# power_converter.net
KiCad netlist of a schematic drawn in EAGLE
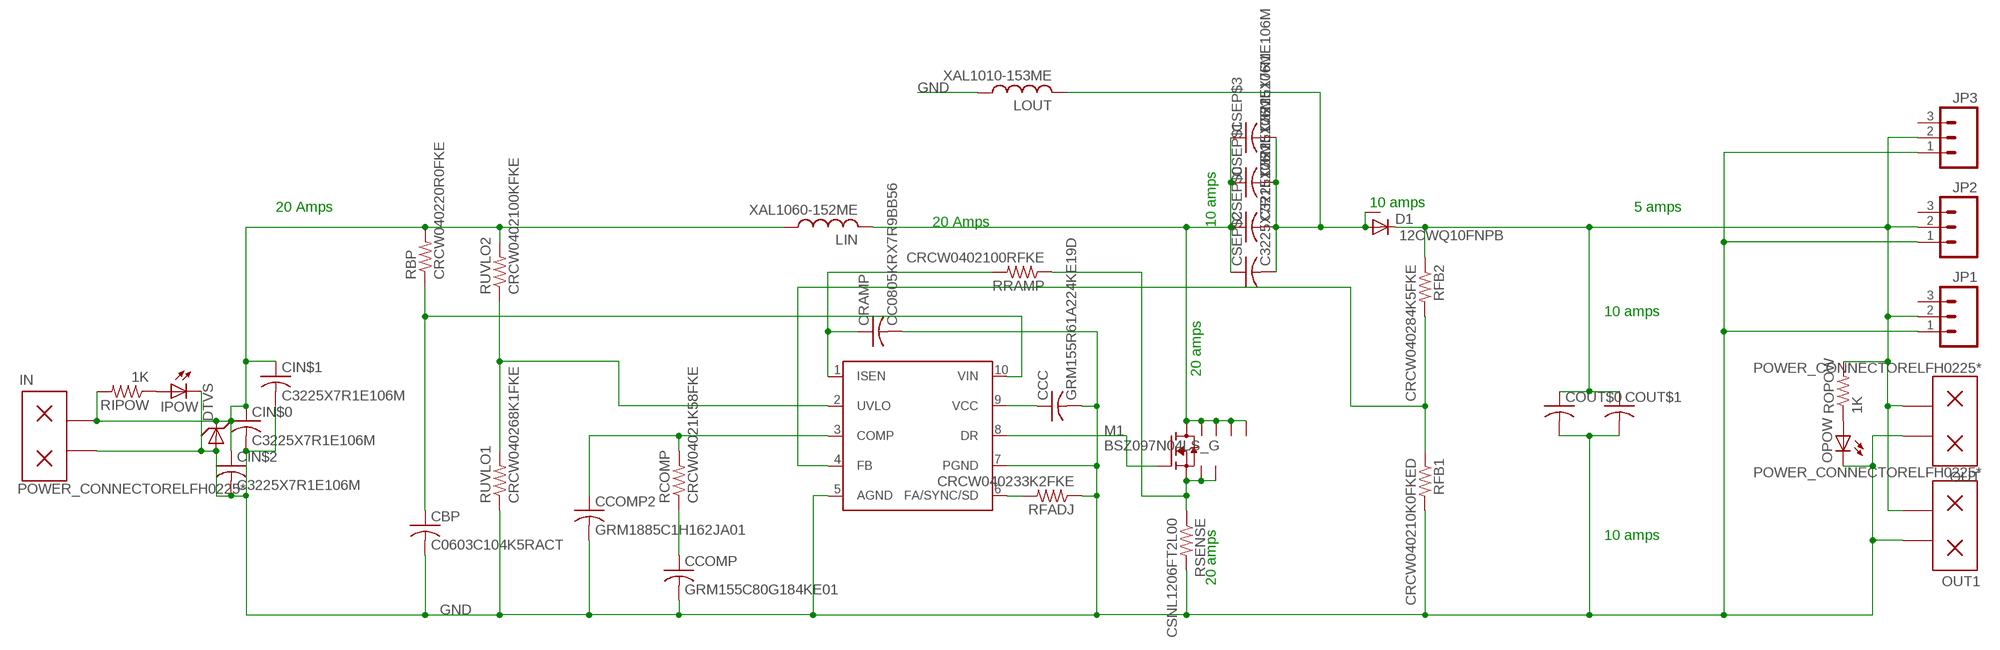
[diagram p0: schematic, sheet 1]

(export (version "E")
  (design (tool "Eeschema 10.0.6"))
  (components
    (comp (ref "CBP")
      (value "C0603C104K5RACT")
      (footprint "eagle-import:C0603")
      (libsource (lib "eagle-import") (part "resistor_C-USC0603"))
    )
    (comp (ref "CCC")
      (value "GRM155R61A224KE19D")
      (footprint "eagle-import:C0402")
      (libsource (lib "eagle-import") (part "resistor_C-USC0402"))
    )
    (comp (ref "CCOMP")
      (value "GRM155C80G184KE01")
      (footprint "eagle-import:C0402")
      (libsource (lib "eagle-import") (part "resistor_C-USC0402"))
    )
    (comp (ref "CCOMP2")
      (value "GRM1885C1H162JA01")
      (footprint "eagle-import:C0603")
      (libsource (lib "eagle-import") (part "resistor_C-USC0603"))
    )
    (comp (ref "CIN$0")
      (value "C3225X7R1E106M")
      (footprint "eagle-import:C1210")
      (libsource (lib "eagle-import") (part "resistor_C-USC1210"))
    )
    (comp (ref "CIN$1")
      (value "C3225X7R1E106M")
      (footprint "eagle-import:C1210")
      (libsource (lib "eagle-import") (part "resistor_C-USC1210"))
    )
    (comp (ref "CIN$2")
      (value "C3225X7R1E106M")
      (footprint "eagle-import:C1210")
      (libsource (lib "eagle-import") (part "resistor_C-USC1210"))
    )
    (comp (ref "COUT$0")
      (value "C-USRR71C331MDN1")
      (footprint "eagle-import:RR71C331MDN1")
      (libsource (lib "eagle-import") (part "C-USRR71C331MDN1"))
    )
    (comp (ref "COUT$1")
      (value "C-USRR71C331MDN1")
      (footprint "eagle-import:RR71C331MDN1")
      (libsource (lib "eagle-import") (part "C-USRR71C331MDN1"))
    )
    (comp (ref "CRAMP")
      (value "CC0805KRX7R9BB56")
      (footprint "eagle-import:C0805")
      (libsource (lib "eagle-import") (part "resistor_C-USC0805"))
    )
    (comp (ref "CSEP$0")
      (value "C3225X7R1E106M")
      (footprint "eagle-import:C1210")
      (libsource (lib "eagle-import") (part "resistor_C-USC1210"))
    )
    (comp (ref "CSEP$1")
      (value "C3225X7R1E106M")
      (footprint "eagle-import:C1210")
      (libsource (lib "eagle-import") (part "resistor_C-USC1210"))
    )
    (comp (ref "CSEP$2")
      (value "C3225X7R1E106M")
      (footprint "eagle-import:C1210")
      (libsource (lib "eagle-import") (part "resistor_C-USC1210"))
    )
    (comp (ref "CSEP$3")
      (value "C3225X7R1E106M")
      (footprint "eagle-import:C1210")
      (libsource (lib "eagle-import") (part "resistor_C-USC1210"))
    )
    (comp (ref "D1")
      (value "12CWQ10FNPB")
      (footprint "eagle-import:D-PAK")
      (libsource (lib "eagle-import") (part "VS-12CWQ10FNPBF"))
    )
    (comp (ref "DTVS")
      (value "MMSZ5246BT1G")
      (footprint "eagle-import:SOD-123")
      (libsource (lib "eagle-import") (part "MMSZ5242BT1G"))
    )
    (comp (ref "IN")
      (value "POWER_CONNECTORELFH0225*")
      (footprint "eagle-import:ELFH0225_")
      (libsource (lib "eagle-import") (part "POWER_CONNECTORELFH0225"))
    )
    (comp (ref "IPOW")
      (value "LEDCHIPLED_0805")
      (footprint "eagle-import:CHIPLED_0805")
      (libsource (lib "eagle-import") (part "LEDCHIPLED_0805"))
    )
    (comp (ref "JP1")
      (value "M03PTH")
      (footprint "eagle-import:1X03")
      (libsource (lib "eagle-import") (part "M03PTH"))
    )
    (comp (ref "JP2")
      (value "M03PTH")
      (footprint "eagle-import:1X03")
      (libsource (lib "eagle-import") (part "M03PTH"))
    )
    (comp (ref "JP3")
      (value "M03PTH")
      (footprint "eagle-import:1X03")
      (libsource (lib "eagle-import") (part "M03PTH"))
    )
    (comp (ref "LIN")
      (value "XAL1060-152ME")
      (footprint "eagle-import:1060-152")
      (libsource (lib "eagle-import") (part "L-US1060-152"))
    )
    (comp (ref "LOUT")
      (value "XAL1010-153ME")
      (footprint "eagle-import:1010-153")
      (libsource (lib "eagle-import") (part "L-US1010-153"))
    )
    (comp (ref "M1")
      (value "BSZ097N04LS_G")
      (footprint "eagle-import:PG-TSDSON8")
      (libsource (lib "eagle-import") (part "BSZ097N04LS_G"))
    )
    (comp (ref "OPOW")
      (value "LEDCHIPLED_0805")
      (footprint "eagle-import:CHIPLED_0805")
      (libsource (lib "eagle-import") (part "LEDCHIPLED_0805"))
    )
    (comp (ref "OUT")
      (value "POWER_CONNECTORELFH0225*")
      (footprint "eagle-import:ELFH0225_")
      (libsource (lib "eagle-import") (part "POWER_CONNECTORELFH0225"))
    )
    (comp (ref "OUT1")
      (value "POWER_CONNECTORELFH0225*")
      (footprint "eagle-import:ELFH0225_")
      (libsource (lib "eagle-import") (part "POWER_CONNECTORELFH0225"))
    )
    (comp (ref "RBP")
      (value "CRCW040220R0FKE")
      (footprint "eagle-import:R0402")
      (libsource (lib "eagle-import") (part "R-US_R0402"))
    )
    (comp (ref "RCOMP")
      (value "CRCW04021K58FKE")
      (footprint "eagle-import:R0402")
      (libsource (lib "eagle-import") (part "R-US_R0402"))
    )
    (comp (ref "RFADJ")
      (value "CRCW040233K2FKE")
      (footprint "eagle-import:R0402")
      (libsource (lib "eagle-import") (part "R-US_R0402"))
    )
    (comp (ref "RFB1")
      (value "CRCW040210K0FKED")
      (footprint "eagle-import:R0402")
      (libsource (lib "eagle-import") (part "R-US_R0402"))
    )
    (comp (ref "RFB2")
      (value "CRCW040284K5FKE")
      (footprint "eagle-import:R0402")
      (libsource (lib "eagle-import") (part "R-US_R0402"))
    )
    (comp (ref "RIPOW")
      (value "1K")
      (footprint "eagle-import:R1206")
      (libsource (lib "eagle-import") (part "R-US_R1206"))
    )
    (comp (ref "ROPOW")
      (value "1K")
      (footprint "eagle-import:R1206")
      (libsource (lib "eagle-import") (part "R-US_R1206"))
    )
    (comp (ref "RRAMP")
      (value "CRCW0402100RFKE")
      (footprint "eagle-import:R0402")
      (libsource (lib "eagle-import") (part "R-US_R0402"))
    )
    (comp (ref "RSENSE")
      (value "CSNL1206FT2L00")
      (footprint "eagle-import:M1206")
      (libsource (lib "eagle-import") (part "R-US_M1206"))
    )
    (comp (ref "RUVLO1")
      (value "CRCW040268K1FKE")
      (footprint "eagle-import:R0402")
      (libsource (lib "eagle-import") (part "R-US_R0402"))
    )
    (comp (ref "RUVLO2")
      (value "CRCW0402100KFKE")
      (footprint "eagle-import:R0402")
      (libsource (lib "eagle-import") (part "R-US_R0402"))
    )
    (comp (ref "U$1")
      (value "LM3481")
      (footprint "eagle-import:MSOP10")
      (libsource (lib "eagle-import") (part "LM3481"))
    )
  )
  (nets
    (net (code "1") (name "/GND") (class "Default")
      (node (ref "CBP") (pin "2") (pinfunction "2_2") (pintype "passive"))
      (node (ref "CCC") (pin "2") (pinfunction "2_2") (pintype "passive"))
      (node (ref "CCOMP") (pin "2") (pinfunction "2_2") (pintype "passive"))
      (node (ref "CCOMP2") (pin "2") (pinfunction "2_2") (pintype "passive"))
      (node (ref "CIN$0") (pin "2") (pinfunction "2_2") (pintype "passive"))
      (node (ref "CIN$1") (pin "2") (pinfunction "2_2") (pintype "passive"))
      (node (ref "CIN$2") (pin "2") (pinfunction "2_2") (pintype "passive"))
      (node (ref "COUT$0") (pin "-") (pinfunction "2_-") (pintype "passive"))
      (node (ref "COUT$1") (pin "-") (pinfunction "2_-") (pintype "passive"))
      (node (ref "CRAMP") (pin "2") (pinfunction "2_2") (pintype "passive"))
      (node (ref "DTVS") (pin "ANODE") (pinfunction "A_ANODE") (pintype "passive"))
      (node (ref "IN") (pin "P$1") (pinfunction "P$2_P$1") (pintype "bidirectional"))
      (node (ref "IPOW") (pin "C") (pinfunction "C_C") (pintype "passive"))
      (node (ref "JP1") (pin "1") (pinfunction "1_1") (pintype "passive"))
      (node (ref "JP2") (pin "1") (pinfunction "1_1") (pintype "passive"))
      (node (ref "JP3") (pin "1") (pinfunction "1_1") (pintype "passive"))
      (node (ref "LOUT") (pin "P$1") (pinfunction "1_P$1") (pintype "passive"))
      (node (ref "OPOW") (pin "C") (pinfunction "C_C") (pintype "passive"))
      (node (ref "OUT") (pin "P$2") (pinfunction "P$1_P$2") (pintype "bidirectional"))
      (node (ref "OUT1") (pin "P$2") (pinfunction "P$1_P$2") (pintype "bidirectional"))
      (node (ref "RFADJ") (pin "1") (pinfunction "1_1") (pintype "passive"))
      (node (ref "RFB1") (pin "2") (pinfunction "2_2") (pintype "passive"))
      (node (ref "RSENSE") (pin "2") (pinfunction "2_2") (pintype "passive"))
      (node (ref "RUVLO1") (pin "1") (pinfunction "1_1") (pintype "passive"))
      (node (ref "U$1") (pin "5") (pinfunction "AGND_5") (pintype "bidirectional"))
      (node (ref "U$1") (pin "7") (pinfunction "PGND_7") (pintype "bidirectional"))
    )
    (net (code "2") (name "Net-(CCOMP-Pad1)") (class "Default")
      (node (ref "CCOMP") (pin "1") (pinfunction "1_1") (pintype "passive"))
      (node (ref "RCOMP") (pin "1") (pinfunction "1_1") (pintype "passive"))
    )
    (net (code "3") (name "Net-(COUT$0-1)") (class "Default")
      (node (ref "COUT$0") (pin "+") (pinfunction "1_+") (pintype "passive"))
      (node (ref "COUT$1") (pin "+") (pinfunction "1_+") (pintype "passive"))
      (node (ref "D1") (pin "CATHODE") (pinfunction "C_CATHODE") (pintype "passive"))
      (node (ref "JP1") (pin "2") (pinfunction "2_2") (pintype "passive"))
      (node (ref "JP2") (pin "2") (pinfunction "2_2") (pintype "passive"))
      (node (ref "JP3") (pin "2") (pinfunction "2_2") (pintype "passive"))
      (node (ref "OUT") (pin "P$1") (pinfunction "P$2_P$1") (pintype "bidirectional"))
      (node (ref "OUT1") (pin "P$1") (pinfunction "P$2_P$1") (pintype "bidirectional"))
      (node (ref "RFB2") (pin "1") (pinfunction "1_1") (pintype "passive"))
      (node (ref "ROPOW") (pin "2") (pinfunction "2_2") (pintype "passive"))
    )
    (net (code "4") (name "Net-(D1-A)") (class "Default")
      (node (ref "CSEP$0") (pin "2") (pinfunction "2_2") (pintype "passive"))
      (node (ref "CSEP$1") (pin "2") (pinfunction "2_2") (pintype "passive"))
      (node (ref "CSEP$2") (pin "2") (pinfunction "2_2") (pintype "passive"))
      (node (ref "CSEP$3") (pin "2") (pinfunction "2_2") (pintype "passive"))
      (node (ref "D1") (pin "ANODE$0") (pinfunction "A_ANODE$0") (pintype "passive"))
      (node (ref "D1") (pin "ANODE$1") (pinfunction "A1_ANODE$1") (pintype "passive"))
      (node (ref "LOUT") (pin "P$2") (pinfunction "2_P$2") (pintype "passive"))
    )
    (net (code "5") (name "Net-(DTVS-C)") (class "Default")
      (node (ref "CIN$0") (pin "1") (pinfunction "1_1") (pintype "passive"))
      (node (ref "CIN$1") (pin "1") (pinfunction "1_1") (pintype "passive"))
      (node (ref "CIN$2") (pin "1") (pinfunction "1_1") (pintype "passive"))
      (node (ref "DTVS") (pin "CATHODE") (pinfunction "C_CATHODE") (pintype "passive"))
      (node (ref "IN") (pin "P$2") (pinfunction "P$1_P$2") (pintype "bidirectional"))
      (node (ref "LIN") (pin "P$1") (pinfunction "1_P$1") (pintype "passive"))
      (node (ref "RBP") (pin "2") (pinfunction "2_2") (pintype "passive"))
      (node (ref "RIPOW") (pin "2") (pinfunction "2_2") (pintype "passive"))
      (node (ref "RUVLO2") (pin "2") (pinfunction "2_2") (pintype "passive"))
    )
    (net (code "6") (name "Net-(IPOW-PadA)") (class "Default")
      (node (ref "IPOW") (pin "A") (pinfunction "A_A") (pintype "passive"))
      (node (ref "RIPOW") (pin "1") (pinfunction "1_1") (pintype "passive"))
    )
    (net (code "7") (name "Net-(LIN-2)") (class "Default")
      (node (ref "CSEP$0") (pin "1") (pinfunction "1_1") (pintype "passive"))
      (node (ref "CSEP$1") (pin "1") (pinfunction "1_1") (pintype "passive"))
      (node (ref "CSEP$2") (pin "1") (pinfunction "1_1") (pintype "passive"))
      (node (ref "CSEP$3") (pin "1") (pinfunction "1_1") (pintype "passive"))
      (node (ref "LIN") (pin "P$2") (pinfunction "2_P$2") (pintype "passive"))
      (node (ref "M1") (pin "D$0") (pinfunction "D_D$0") (pintype "passive"))
      (node (ref "M1") (pin "D$1") (pinfunction "D$1_D$1") (pintype "passive"))
      (node (ref "M1") (pin "D$2") (pinfunction "D$2_D$2") (pintype "passive"))
      (node (ref "M1") (pin "D$3") (pinfunction "D$3_D$3") (pintype "passive"))
      (node (ref "M1") (pin "D$4") (pinfunction "D$4_D$4") (pintype "passive"))
    )
    (net (code "8") (name "Net-(M1-S)") (class "Default")
      (node (ref "M1") (pin "S$0") (pinfunction "S_S$0") (pintype "passive"))
      (node (ref "M1") (pin "S$1") (pinfunction "S$1_S$1") (pintype "passive"))
      (node (ref "M1") (pin "S$2") (pinfunction "S$2_S$2") (pintype "passive"))
      (node (ref "RRAMP") (pin "1") (pinfunction "1_1") (pintype "passive"))
      (node (ref "RSENSE") (pin "1") (pinfunction "1_1") (pintype "passive"))
    )
    (net (code "9") (name "Net-(OPOW-PadA)") (class "Default")
      (node (ref "OPOW") (pin "A") (pinfunction "A_A") (pintype "passive"))
      (node (ref "ROPOW") (pin "1") (pinfunction "1_1") (pintype "passive"))
    )
    (net (code "10") (name "Net-(U$1-COMP)") (class "Default")
      (node (ref "CCOMP2") (pin "1") (pinfunction "1_1") (pintype "passive"))
      (node (ref "RCOMP") (pin "2") (pinfunction "2_2") (pintype "passive"))
      (node (ref "U$1") (pin "3") (pinfunction "COMP_3") (pintype "bidirectional"))
    )
    (net (code "11") (name "Net-(U$1-DR)") (class "Default")
      (node (ref "M1") (pin "G") (pinfunction "G_G") (pintype "passive"))
      (node (ref "U$1") (pin "8") (pinfunction "DR_8") (pintype "bidirectional"))
    )
    (net (code "12") (name "Net-(U$1-FA{slash}SYNC{slash}SD)") (class "Default")
      (node (ref "RFADJ") (pin "2") (pinfunction "2_2") (pintype "passive"))
      (node (ref "U$1") (pin "6") (pinfunction "FA/SYNC/SD_6") (pintype "bidirectional"))
    )
    (net (code "13") (name "Net-(U$1-FB)") (class "Default")
      (node (ref "RFB1") (pin "1") (pinfunction "1_1") (pintype "passive"))
      (node (ref "RFB2") (pin "2") (pinfunction "2_2") (pintype "passive"))
      (node (ref "U$1") (pin "4") (pinfunction "FB_4") (pintype "bidirectional"))
    )
    (net (code "14") (name "Net-(U$1-ISEN)") (class "Default")
      (node (ref "CRAMP") (pin "1") (pinfunction "1_1") (pintype "passive"))
      (node (ref "RRAMP") (pin "2") (pinfunction "2_2") (pintype "passive"))
      (node (ref "U$1") (pin "1") (pinfunction "ISEN_1") (pintype "bidirectional"))
    )
    (net (code "15") (name "Net-(U$1-UVLO)") (class "Default")
      (node (ref "RUVLO1") (pin "2") (pinfunction "2_2") (pintype "passive"))
      (node (ref "RUVLO2") (pin "1") (pinfunction "1_1") (pintype "passive"))
      (node (ref "U$1") (pin "2") (pinfunction "UVLO_2") (pintype "bidirectional"))
    )
    (net (code "16") (name "Net-(U$1-VCC)") (class "Default")
      (node (ref "CCC") (pin "1") (pinfunction "1_1") (pintype "passive"))
      (node (ref "U$1") (pin "9") (pinfunction "VCC_9") (pintype "bidirectional"))
    )
    (net (code "17") (name "Net-(U$1-VIN)") (class "Default")
      (node (ref "CBP") (pin "1") (pinfunction "1_1") (pintype "passive"))
      (node (ref "RBP") (pin "1") (pinfunction "1_1") (pintype "passive"))
      (node (ref "U$1") (pin "10") (pinfunction "VIN_10") (pintype "bidirectional"))
    )
    (net (code "18") (name "unconnected-(JP1-Pad3)") (class "Default")
      (node (ref "JP1") (pin "3") (pinfunction "3_3") (pintype "passive"))
    )
    (net (code "19") (name "unconnected-(JP2-Pad3)") (class "Default")
      (node (ref "JP2") (pin "3") (pinfunction "3_3") (pintype "passive"))
    )
    (net (code "20") (name "unconnected-(JP3-Pad3)") (class "Default")
      (node (ref "JP3") (pin "3") (pinfunction "3_3") (pintype "passive"))
    )
  )
)
